# PlantSensorHead.net
KiCad netlist of a schematic drawn in EAGLE
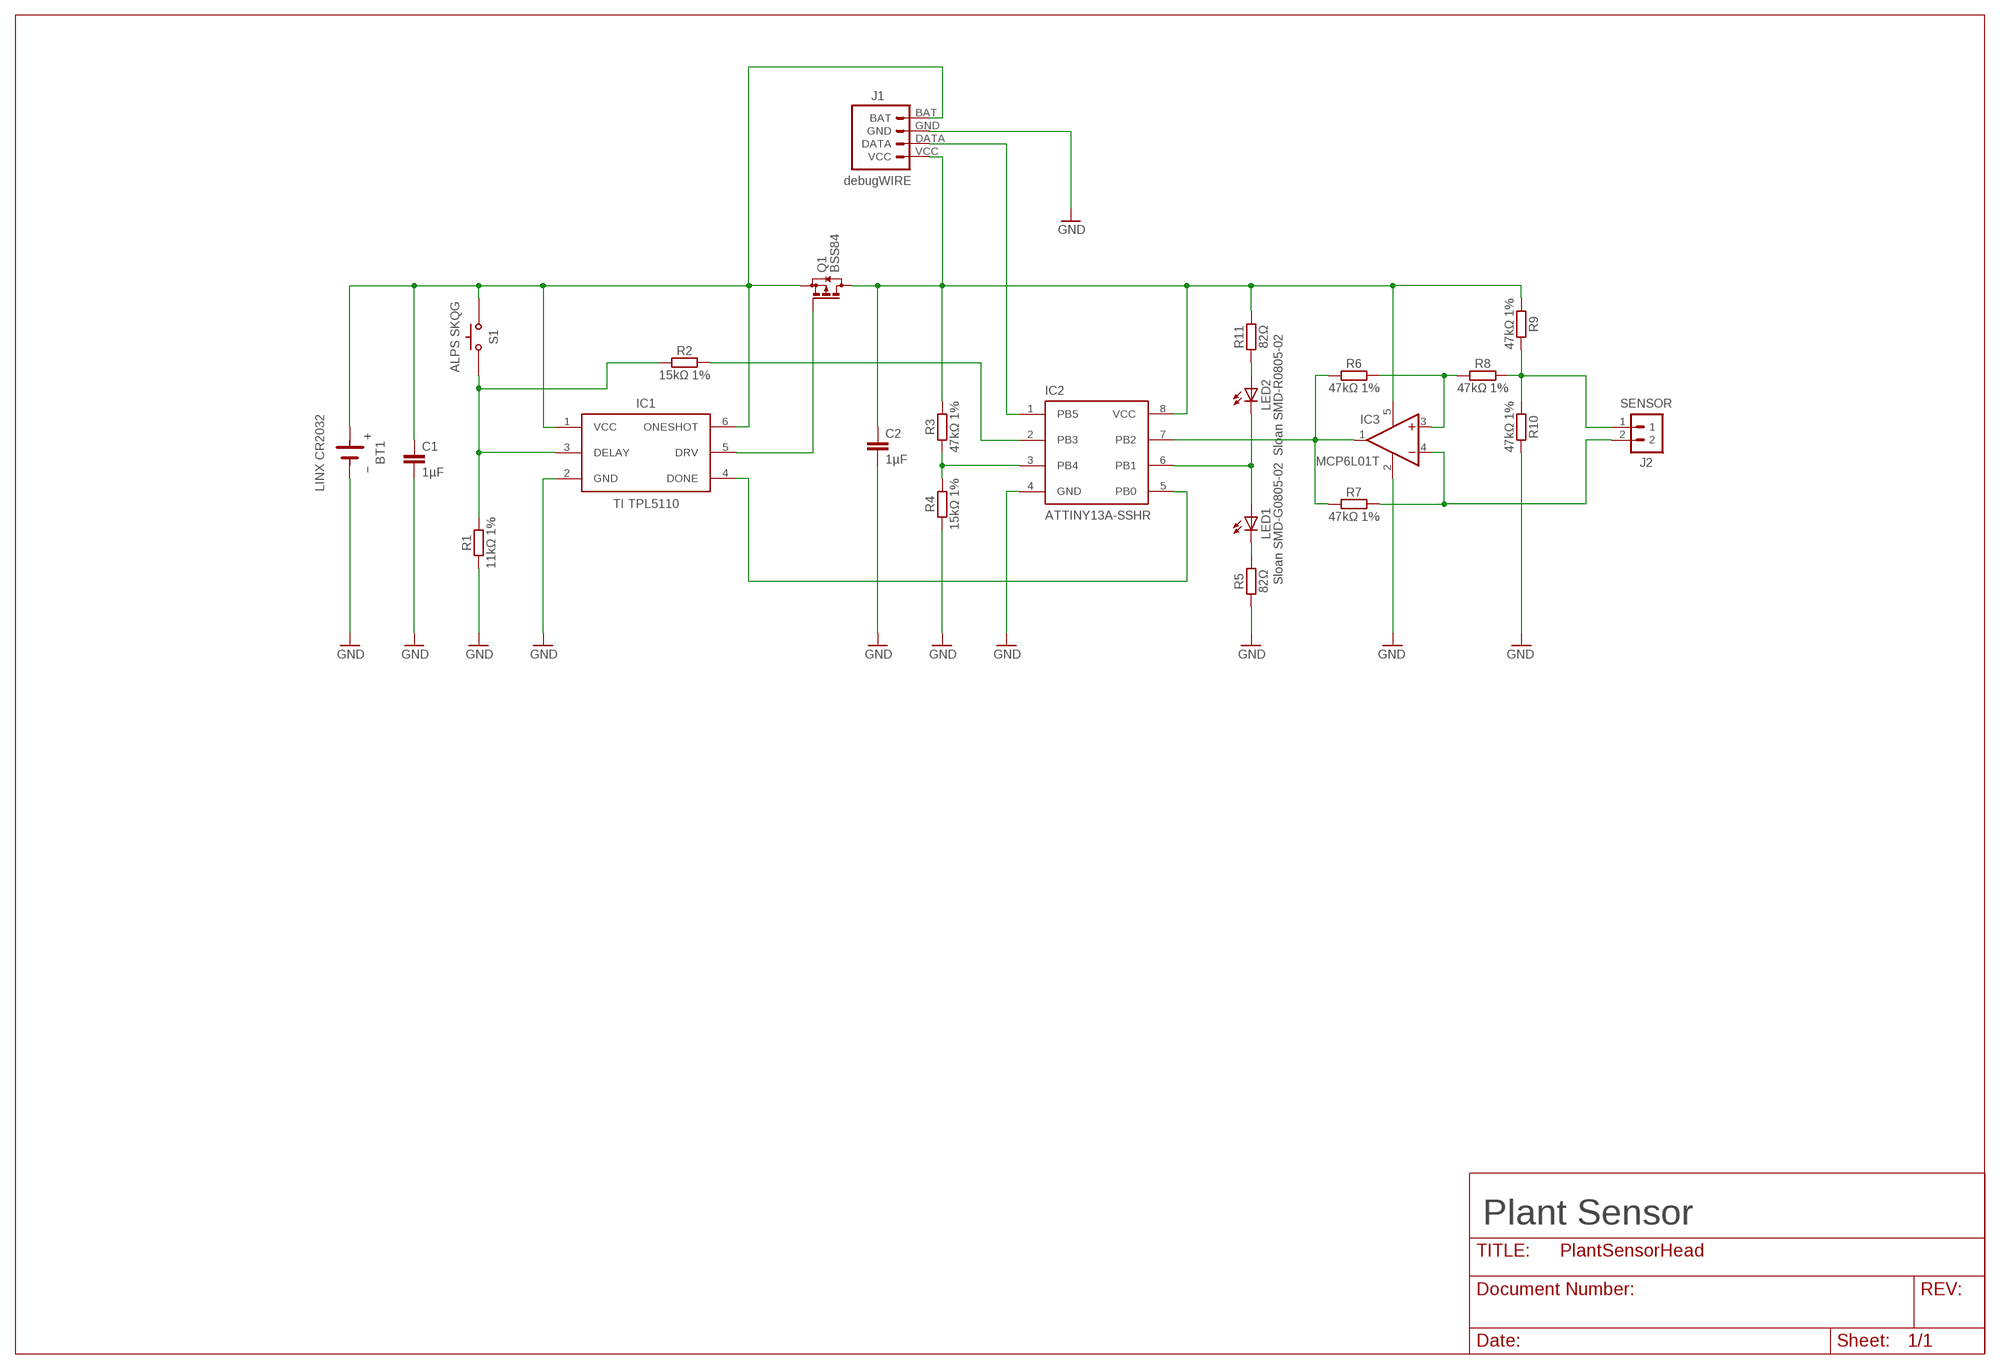
[diagram p0: schematic, sheet 1]

(export (version "E")
  (design (tool "Eeschema 10.0.6"))
  (components
    (comp (ref "BT1")
      (value "LINX CR2032")
      (footprint "eagle-import:LINX-BAT-HLD-001")
      (libsource (lib "eagle-import") (part "LINX-CR2032-BATTERY-HOLDER"))
    )
    (comp (ref "C1")
      (value "1µF")
      (footprint "eagle-import:CAPACITOR-0805-MURATA-GRM-21")
      (libsource (lib "eagle-import") (part "C0805-MURATA-GRM-21"))
    )
    (comp (ref "C2")
      (value "1µF")
      (footprint "eagle-import:CAPACITOR-0805-MURATA-GRM-21")
      (libsource (lib "eagle-import") (part "C0805-MURATA-GRM-21"))
    )
    (comp (ref "IC1")
      (value "TI TPL5110")
      (footprint "eagle-import:SOT23-6L")
      (libsource (lib "eagle-import") (part "TPL5110SOT"))
    )
    (comp (ref "IC2")
      (value "ATTINY13A-SSHR")
      (footprint "eagle-import:SO08_015_JEDEC")
      (libsource (lib "eagle-import") (part "ATTINY13SO08"))
    )
    (comp (ref "IC3")
      (value "MCP6L01T")
      (footprint "eagle-import:SOT23-5")
      (libsource (lib "eagle-import") (part "MCP601OT"))
    )
    (comp (ref "J1")
      (value "debugWIRE")
      (footprint "eagle-import:CON-PADS-DEBUG-WIRE-50")
      (libsource (lib "eagle-import") (part "CON-DEBUGWIRE-SMD-50"))
    )
    (comp (ref "J2")
      (value "SENSOR")
      (footprint "eagle-import:CON_PADS_2XWIRE")
      (libsource (lib "eagle-import") (part "CON_2X1WIREPADS"))
    )
    (comp (ref "LED1")
      (value "Sloan SMD-G0805-02")
      (footprint "eagle-import:LED-0805-SLOAN")
      (libsource (lib "eagle-import") (part "LED0805-SLOAN"))
    )
    (comp (ref "LED2")
      (value "Sloan SMD-R0805-02")
      (footprint "eagle-import:LED-0805-SLOAN")
      (libsource (lib "eagle-import") (part "LED0805-SLOAN"))
    )
    (comp (ref "Q1")
      (value "BSS84")
      (footprint "eagle-import:SOT23")
      (libsource (lib "eagle-import") (part "BSS84"))
    )
    (comp (ref "R1")
      (value "11kΩ 1%")
      (footprint "eagle-import:RESISTOR-0805-KOA-RK73-2A")
      (libsource (lib "eagle-import") (part "RESISTOR0805-KOA-RK73-2A"))
    )
    (comp (ref "R2")
      (value "15kΩ 1%")
      (footprint "eagle-import:RESISTOR-0805-KOA-RK73-2A")
      (libsource (lib "eagle-import") (part "RESISTOR0805-KOA-RK73-2A"))
    )
    (comp (ref "R3")
      (value "47kΩ 1%")
      (footprint "eagle-import:RESISTOR-0805-KOA-RK73-2A")
      (libsource (lib "eagle-import") (part "RESISTOR0805-KOA-RK73-2A"))
    )
    (comp (ref "R4")
      (value "15kΩ 1%")
      (footprint "eagle-import:RESISTOR-0805-KOA-RK73-2A")
      (libsource (lib "eagle-import") (part "RESISTOR0805-KOA-RK73-2A"))
    )
    (comp (ref "R5")
      (value "82Ω")
      (footprint "eagle-import:RESISTOR-0805-KOA-RK73-2A")
      (libsource (lib "eagle-import") (part "RESISTOR0805-KOA-RK73-2A"))
    )
    (comp (ref "R6")
      (value "47kΩ 1%")
      (footprint "eagle-import:RESISTOR-0805-KOA-RK73-2A")
      (libsource (lib "eagle-import") (part "RESISTOR0805-KOA-RK73-2A"))
    )
    (comp (ref "R7")
      (value "47kΩ 1%")
      (footprint "eagle-import:RESISTOR-0805-KOA-RK73-2A")
      (libsource (lib "eagle-import") (part "RESISTOR0805-KOA-RK73-2A"))
    )
    (comp (ref "R8")
      (value "47kΩ 1%")
      (footprint "eagle-import:RESISTOR-0805-KOA-RK73-2A")
      (libsource (lib "eagle-import") (part "RESISTOR0805-KOA-RK73-2A"))
    )
    (comp (ref "R9")
      (value "47kΩ 1%")
      (footprint "eagle-import:RESISTOR-0805-KOA-RK73-2A")
      (libsource (lib "eagle-import") (part "RESISTOR0805-KOA-RK73-2A"))
    )
    (comp (ref "R10")
      (value "47kΩ 1%")
      (footprint "eagle-import:RESISTOR-0805-KOA-RK73-2A")
      (libsource (lib "eagle-import") (part "RESISTOR0805-KOA-RK73-2A"))
    )
    (comp (ref "R11")
      (value "82Ω")
      (footprint "eagle-import:RESISTOR-0805-KOA-RK73-2A")
      (libsource (lib "eagle-import") (part "RESISTOR0805-KOA-RK73-2A"))
    )
    (comp (ref "S1")
      (value "ALPS SKQG")
      (footprint "eagle-import:ALPS_SKQGAKE010")
      (libsource (lib "eagle-import") (part "ALPS_SKQG_BUTTONAKE010"))
    )
  )
  (nets
    (net (code "1") (name "GND") (class "Default")
      (node (ref "BT1") (pin "GND") (pinfunction "GND_GND") (pintype "power_in"))
      (node (ref "C1") (pin "2") (pinfunction "2_2") (pintype "passive"))
      (node (ref "C2") (pin "2") (pinfunction "2_2") (pintype "passive"))
      (node (ref "IC1") (pin "2") (pinfunction "GND_2") (pintype "power_in"))
      (node (ref "IC2") (pin "4") (pinfunction "GND_4") (pintype "power_in"))
      (node (ref "IC3") (pin "2") (pinfunction "V-_2") (pintype "power_in"))
      (node (ref "J1") (pin "GND") (pinfunction "GND_GND") (pintype "power_in"))
      (node (ref "R1") (pin "1") (pinfunction "1_1") (pintype "passive"))
      (node (ref "R10") (pin "1") (pinfunction "1_1") (pintype "passive"))
      (node (ref "R4") (pin "1") (pinfunction "1_1") (pintype "passive"))
      (node (ref "R5") (pin "1") (pinfunction "1_1") (pintype "passive"))
    )
    (net (code "2") (name "Net-(IC1-DELAY)") (class "Default")
      (node (ref "IC1") (pin "3") (pinfunction "DELAY_3") (pintype "input"))
      (node (ref "R1") (pin "2") (pinfunction "2_2") (pintype "passive"))
      (node (ref "R2") (pin "1") (pinfunction "1_1") (pintype "passive"))
      (node (ref "S1") (pin "1") (pinfunction "1_1") (pintype "passive"))
      (node (ref "S1") (pin "2") (pinfunction "1_2") (pintype "passive"))
    )
    (net (code "3") (name "Net-(IC1-DONE)") (class "Default")
      (node (ref "IC1") (pin "4") (pinfunction "DONE_4") (pintype "input"))
      (node (ref "IC2") (pin "5") (pinfunction "PB0_5") (pintype "bidirectional"))
    )
    (net (code "4") (name "Net-(IC1-DRV)") (class "Default")
      (node (ref "IC1") (pin "5") (pinfunction "DRV_5") (pintype "output"))
      (node (ref "Q1") (pin "1") (pinfunction "G_1") (pintype "passive"))
    )
    (net (code "5") (name "Net-(IC1-ONESHOT)") (class "Default")
      (node (ref "BT1") (pin "VDD1") (pinfunction "VDD_VDD1") (pintype "power_in"))
      (node (ref "BT1") (pin "VDD2") (pinfunction "VDD_VDD2") (pintype "power_in"))
      (node (ref "C1") (pin "1") (pinfunction "1_1") (pintype "passive"))
      (node (ref "IC1") (pin "1") (pinfunction "VCC_1") (pintype "power_in"))
      (node (ref "IC1") (pin "6") (pinfunction "ONESHOT_6") (pintype "input"))
      (node (ref "J1") (pin "BAT") (pinfunction "BAT_BAT") (pintype "power_in"))
      (node (ref "Q1") (pin "2") (pinfunction "S_2") (pintype "passive"))
      (node (ref "S1") (pin "3") (pinfunction "2_3") (pintype "passive"))
      (node (ref "S1") (pin "4") (pinfunction "2_4") (pintype "passive"))
    )
    (net (code "6") (name "Net-(IC2-PB1)") (class "Default")
      (node (ref "IC2") (pin "6") (pinfunction "PB1_6") (pintype "bidirectional"))
      (node (ref "LED1") (pin "A") (pinfunction "A_A") (pintype "passive"))
      (node (ref "LED2") (pin "C") (pinfunction "C_C") (pintype "passive"))
    )
    (net (code "7") (name "Net-(IC2-PB2)") (class "Default")
      (node (ref "IC2") (pin "7") (pinfunction "PB2_7") (pintype "bidirectional"))
      (node (ref "IC3") (pin "1") (pinfunction "OUT_1") (pintype "output"))
      (node (ref "R6") (pin "2") (pinfunction "2_2") (pintype "passive"))
      (node (ref "R7") (pin "2") (pinfunction "2_2") (pintype "passive"))
    )
    (net (code "8") (name "Net-(IC2-PB3)") (class "Default")
      (node (ref "IC2") (pin "2") (pinfunction "PB3_2") (pintype "bidirectional"))
      (node (ref "R2") (pin "2") (pinfunction "2_2") (pintype "passive"))
    )
    (net (code "9") (name "Net-(IC2-PB4)") (class "Default")
      (node (ref "IC2") (pin "3") (pinfunction "PB4_3") (pintype "bidirectional"))
      (node (ref "R3") (pin "1") (pinfunction "1_1") (pintype "passive"))
      (node (ref "R4") (pin "2") (pinfunction "2_2") (pintype "passive"))
    )
    (net (code "10") (name "Net-(IC2-PB5)") (class "Default")
      (node (ref "IC2") (pin "1") (pinfunction "PB5_1") (pintype "bidirectional"))
      (node (ref "J1") (pin "DATA") (pinfunction "DATA_DATA") (pintype "bidirectional"))
    )
    (net (code "11") (name "Net-(IC2-VCC)") (class "Default")
      (node (ref "C2") (pin "1") (pinfunction "1_1") (pintype "passive"))
      (node (ref "IC2") (pin "8") (pinfunction "VCC_8") (pintype "power_in"))
      (node (ref "IC3") (pin "5") (pinfunction "V+_5") (pintype "power_in"))
      (node (ref "J1") (pin "VCC") (pinfunction "VCC_VCC") (pintype "power_in"))
      (node (ref "Q1") (pin "3") (pinfunction "D_3") (pintype "passive"))
      (node (ref "R11") (pin "2") (pinfunction "2_2") (pintype "passive"))
      (node (ref "R3") (pin "2") (pinfunction "2_2") (pintype "passive"))
      (node (ref "R9") (pin "2") (pinfunction "2_2") (pintype "passive"))
    )
    (net (code "12") (name "Net-(IC3-+IN)") (class "Default")
      (node (ref "IC3") (pin "3") (pinfunction "+IN_3") (pintype "input"))
      (node (ref "R6") (pin "1") (pinfunction "1_1") (pintype "passive"))
      (node (ref "R8") (pin "2") (pinfunction "2_2") (pintype "passive"))
    )
    (net (code "13") (name "Net-(IC3--IN)") (class "Default")
      (node (ref "IC3") (pin "4") (pinfunction "-IN_4") (pintype "input"))
      (node (ref "J2") (pin "2") (pinfunction "2_2") (pintype "passive"))
      (node (ref "R7") (pin "1") (pinfunction "1_1") (pintype "passive"))
    )
    (net (code "14") (name "Net-(J2-Pad1)") (class "Default")
      (node (ref "J2") (pin "1") (pinfunction "1_1") (pintype "passive"))
      (node (ref "R10") (pin "2") (pinfunction "2_2") (pintype "passive"))
      (node (ref "R8") (pin "1") (pinfunction "1_1") (pintype "passive"))
      (node (ref "R9") (pin "1") (pinfunction "1_1") (pintype "passive"))
    )
    (net (code "15") (name "Net-(LED1-PadC)") (class "Default")
      (node (ref "LED1") (pin "C") (pinfunction "C_C") (pintype "passive"))
      (node (ref "R5") (pin "2") (pinfunction "2_2") (pintype "passive"))
    )
    (net (code "16") (name "Net-(LED2-PadA)") (class "Default")
      (node (ref "LED2") (pin "A") (pinfunction "A_A") (pintype "passive"))
      (node (ref "R11") (pin "1") (pinfunction "1_1") (pintype "passive"))
    )
  )
)
